# Alberts_NeoPixel_Ring.net
KiCad netlist of a schematic drawn in EAGLE
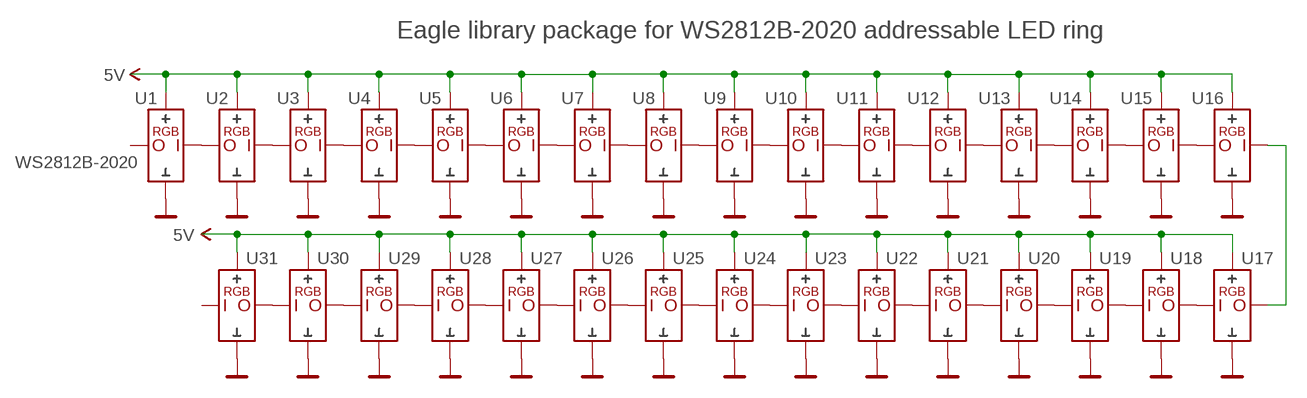
[diagram p0: schematic, sheet 1]

(export (version "E")
  (design (tool "Eeschema 10.0.6"))
  (components
    (comp (ref "U1")
      (value "WS2812B-2020")
      (footprint "eagle-import:LED-WS2812B-2020-RING")
      (libsource (lib "eagle-import") (part "LED-ADDRESSABLE16MM"))
    )
    (comp (ref "U2")
      (value "LED-ADDRESSABLE16MM")
      (footprint "eagle-import:LED-WS2812B-2020-RING")
      (libsource (lib "eagle-import") (part "LED-ADDRESSABLE16MM"))
    )
    (comp (ref "U3")
      (value "LED-ADDRESSABLE16MM")
      (footprint "eagle-import:LED-WS2812B-2020-RING")
      (libsource (lib "eagle-import") (part "LED-ADDRESSABLE16MM"))
    )
    (comp (ref "U4")
      (value "LED-ADDRESSABLE16MM")
      (footprint "eagle-import:LED-WS2812B-2020-RING")
      (libsource (lib "eagle-import") (part "LED-ADDRESSABLE16MM"))
    )
    (comp (ref "U5")
      (value "LED-ADDRESSABLE16MM")
      (footprint "eagle-import:LED-WS2812B-2020-RING")
      (libsource (lib "eagle-import") (part "LED-ADDRESSABLE16MM"))
    )
    (comp (ref "U6")
      (value "LED-ADDRESSABLE16MM")
      (footprint "eagle-import:LED-WS2812B-2020-RING")
      (libsource (lib "eagle-import") (part "LED-ADDRESSABLE16MM"))
    )
    (comp (ref "U7")
      (value "LED-ADDRESSABLE16MM")
      (footprint "eagle-import:LED-WS2812B-2020-RING")
      (libsource (lib "eagle-import") (part "LED-ADDRESSABLE16MM"))
    )
    (comp (ref "U8")
      (value "LED-ADDRESSABLE16MM")
      (footprint "eagle-import:LED-WS2812B-2020-RING")
      (libsource (lib "eagle-import") (part "LED-ADDRESSABLE16MM"))
    )
    (comp (ref "U9")
      (value "LED-ADDRESSABLE16MM")
      (footprint "eagle-import:LED-WS2812B-2020-RING")
      (libsource (lib "eagle-import") (part "LED-ADDRESSABLE16MM"))
    )
    (comp (ref "U10")
      (value "LED-ADDRESSABLE16MM")
      (footprint "eagle-import:LED-WS2812B-2020-RING")
      (libsource (lib "eagle-import") (part "LED-ADDRESSABLE16MM"))
    )
    (comp (ref "U11")
      (value "LED-ADDRESSABLE16MM")
      (footprint "eagle-import:LED-WS2812B-2020-RING")
      (libsource (lib "eagle-import") (part "LED-ADDRESSABLE16MM"))
    )
    (comp (ref "U12")
      (value "LED-ADDRESSABLE16MM")
      (footprint "eagle-import:LED-WS2812B-2020-RING")
      (libsource (lib "eagle-import") (part "LED-ADDRESSABLE16MM"))
    )
    (comp (ref "U13")
      (value "LED-ADDRESSABLE16MM")
      (footprint "eagle-import:LED-WS2812B-2020-RING")
      (libsource (lib "eagle-import") (part "LED-ADDRESSABLE16MM"))
    )
    (comp (ref "U14")
      (value "LED-ADDRESSABLE16MM")
      (footprint "eagle-import:LED-WS2812B-2020-RING")
      (libsource (lib "eagle-import") (part "LED-ADDRESSABLE16MM"))
    )
    (comp (ref "U15")
      (value "LED-ADDRESSABLE16MM")
      (footprint "eagle-import:LED-WS2812B-2020-RING")
      (libsource (lib "eagle-import") (part "LED-ADDRESSABLE16MM"))
    )
    (comp (ref "U16")
      (value "LED-ADDRESSABLE16MM")
      (footprint "eagle-import:LED-WS2812B-2020-RING")
      (libsource (lib "eagle-import") (part "LED-ADDRESSABLE16MM"))
    )
    (comp (ref "U17")
      (value "LED-ADDRESSABLE16MM")
      (footprint "eagle-import:LED-WS2812B-2020-RING")
      (libsource (lib "eagle-import") (part "LED-ADDRESSABLE16MM"))
    )
    (comp (ref "U18")
      (value "LED-ADDRESSABLE16MM")
      (footprint "eagle-import:LED-WS2812B-2020-RING")
      (libsource (lib "eagle-import") (part "LED-ADDRESSABLE16MM"))
    )
    (comp (ref "U19")
      (value "LED-ADDRESSABLE16MM")
      (footprint "eagle-import:LED-WS2812B-2020-RING")
      (libsource (lib "eagle-import") (part "LED-ADDRESSABLE16MM"))
    )
    (comp (ref "U20")
      (value "LED-ADDRESSABLE16MM")
      (footprint "eagle-import:LED-WS2812B-2020-RING")
      (libsource (lib "eagle-import") (part "LED-ADDRESSABLE16MM"))
    )
    (comp (ref "U21")
      (value "LED-ADDRESSABLE16MM")
      (footprint "eagle-import:LED-WS2812B-2020-RING")
      (libsource (lib "eagle-import") (part "LED-ADDRESSABLE16MM"))
    )
    (comp (ref "U22")
      (value "LED-ADDRESSABLE16MM")
      (footprint "eagle-import:LED-WS2812B-2020-RING")
      (libsource (lib "eagle-import") (part "LED-ADDRESSABLE16MM"))
    )
    (comp (ref "U23")
      (value "LED-ADDRESSABLE16MM")
      (footprint "eagle-import:LED-WS2812B-2020-RING")
      (libsource (lib "eagle-import") (part "LED-ADDRESSABLE16MM"))
    )
    (comp (ref "U24")
      (value "LED-ADDRESSABLE16MM")
      (footprint "eagle-import:LED-WS2812B-2020-RING")
      (libsource (lib "eagle-import") (part "LED-ADDRESSABLE16MM"))
    )
    (comp (ref "U25")
      (value "LED-ADDRESSABLE16MM")
      (footprint "eagle-import:LED-WS2812B-2020-RING")
      (libsource (lib "eagle-import") (part "LED-ADDRESSABLE16MM"))
    )
    (comp (ref "U26")
      (value "LED-ADDRESSABLE16MM")
      (footprint "eagle-import:LED-WS2812B-2020-RING")
      (libsource (lib "eagle-import") (part "LED-ADDRESSABLE16MM"))
    )
    (comp (ref "U27")
      (value "LED-ADDRESSABLE16MM")
      (footprint "eagle-import:LED-WS2812B-2020-RING")
      (libsource (lib "eagle-import") (part "LED-ADDRESSABLE16MM"))
    )
    (comp (ref "U28")
      (value "LED-ADDRESSABLE16MM")
      (footprint "eagle-import:LED-WS2812B-2020-RING")
      (libsource (lib "eagle-import") (part "LED-ADDRESSABLE16MM"))
    )
    (comp (ref "U29")
      (value "LED-ADDRESSABLE16MM")
      (footprint "eagle-import:LED-WS2812B-2020-RING")
      (libsource (lib "eagle-import") (part "LED-ADDRESSABLE16MM"))
    )
    (comp (ref "U30")
      (value "LED-ADDRESSABLE16MM")
      (footprint "eagle-import:LED-WS2812B-2020-RING")
      (libsource (lib "eagle-import") (part "LED-ADDRESSABLE16MM"))
    )
    (comp (ref "U31")
      (value "LED-ADDRESSABLE16MM")
      (footprint "eagle-import:LED-WS2812B-2020-RING")
      (libsource (lib "eagle-import") (part "LED-ADDRESSABLE16MM"))
    )
  )
  (nets
    (net (code "1") (name "/5V") (class "Default")
      (node (ref "U1") (pin "+") (pinfunction "VDD_+") (pintype "bidirectional"))
      (node (ref "U10") (pin "+") (pinfunction "VDD_+") (pintype "bidirectional"))
      (node (ref "U11") (pin "+") (pinfunction "VDD_+") (pintype "bidirectional"))
      (node (ref "U12") (pin "+") (pinfunction "VDD_+") (pintype "bidirectional"))
      (node (ref "U13") (pin "+") (pinfunction "VDD_+") (pintype "bidirectional"))
      (node (ref "U14") (pin "+") (pinfunction "VDD_+") (pintype "bidirectional"))
      (node (ref "U15") (pin "+") (pinfunction "VDD_+") (pintype "bidirectional"))
      (node (ref "U16") (pin "+") (pinfunction "VDD_+") (pintype "bidirectional"))
      (node (ref "U17") (pin "+") (pinfunction "VDD_+") (pintype "bidirectional"))
      (node (ref "U18") (pin "+") (pinfunction "VDD_+") (pintype "bidirectional"))
      (node (ref "U19") (pin "+") (pinfunction "VDD_+") (pintype "bidirectional"))
      (node (ref "U2") (pin "+") (pinfunction "VDD_+") (pintype "bidirectional"))
      (node (ref "U20") (pin "+") (pinfunction "VDD_+") (pintype "bidirectional"))
      (node (ref "U21") (pin "+") (pinfunction "VDD_+") (pintype "bidirectional"))
      (node (ref "U22") (pin "+") (pinfunction "VDD_+") (pintype "bidirectional"))
      (node (ref "U23") (pin "+") (pinfunction "VDD_+") (pintype "bidirectional"))
      (node (ref "U24") (pin "+") (pinfunction "VDD_+") (pintype "bidirectional"))
      (node (ref "U25") (pin "+") (pinfunction "VDD_+") (pintype "bidirectional"))
      (node (ref "U26") (pin "+") (pinfunction "VDD_+") (pintype "bidirectional"))
      (node (ref "U27") (pin "+") (pinfunction "VDD_+") (pintype "bidirectional"))
      (node (ref "U28") (pin "+") (pinfunction "VDD_+") (pintype "bidirectional"))
      (node (ref "U29") (pin "+") (pinfunction "VDD_+") (pintype "bidirectional"))
      (node (ref "U3") (pin "+") (pinfunction "VDD_+") (pintype "bidirectional"))
      (node (ref "U30") (pin "+") (pinfunction "VDD_+") (pintype "bidirectional"))
      (node (ref "U31") (pin "+") (pinfunction "VDD_+") (pintype "bidirectional"))
      (node (ref "U4") (pin "+") (pinfunction "VDD_+") (pintype "bidirectional"))
      (node (ref "U5") (pin "+") (pinfunction "VDD_+") (pintype "bidirectional"))
      (node (ref "U6") (pin "+") (pinfunction "VDD_+") (pintype "bidirectional"))
      (node (ref "U7") (pin "+") (pinfunction "VDD_+") (pintype "bidirectional"))
      (node (ref "U8") (pin "+") (pinfunction "VDD_+") (pintype "bidirectional"))
      (node (ref "U9") (pin "+") (pinfunction "VDD_+") (pintype "bidirectional"))
    )
    (net (code "2") (name "GND") (class "Default")
      (node (ref "U1") (pin "GND") (pinfunction "GND_GND") (pintype "bidirectional"))
      (node (ref "U10") (pin "GND") (pinfunction "GND_GND") (pintype "bidirectional"))
      (node (ref "U11") (pin "GND") (pinfunction "GND_GND") (pintype "bidirectional"))
      (node (ref "U12") (pin "GND") (pinfunction "GND_GND") (pintype "bidirectional"))
      (node (ref "U13") (pin "GND") (pinfunction "GND_GND") (pintype "bidirectional"))
      (node (ref "U14") (pin "GND") (pinfunction "GND_GND") (pintype "bidirectional"))
      (node (ref "U15") (pin "GND") (pinfunction "GND_GND") (pintype "bidirectional"))
      (node (ref "U16") (pin "GND") (pinfunction "GND_GND") (pintype "bidirectional"))
      (node (ref "U17") (pin "GND") (pinfunction "GND_GND") (pintype "bidirectional"))
      (node (ref "U18") (pin "GND") (pinfunction "GND_GND") (pintype "bidirectional"))
      (node (ref "U19") (pin "GND") (pinfunction "GND_GND") (pintype "bidirectional"))
      (node (ref "U2") (pin "GND") (pinfunction "GND_GND") (pintype "bidirectional"))
      (node (ref "U20") (pin "GND") (pinfunction "GND_GND") (pintype "bidirectional"))
      (node (ref "U21") (pin "GND") (pinfunction "GND_GND") (pintype "bidirectional"))
      (node (ref "U22") (pin "GND") (pinfunction "GND_GND") (pintype "bidirectional"))
      (node (ref "U23") (pin "GND") (pinfunction "GND_GND") (pintype "bidirectional"))
      (node (ref "U24") (pin "GND") (pinfunction "GND_GND") (pintype "bidirectional"))
      (node (ref "U25") (pin "GND") (pinfunction "GND_GND") (pintype "bidirectional"))
      (node (ref "U26") (pin "GND") (pinfunction "GND_GND") (pintype "bidirectional"))
      (node (ref "U27") (pin "GND") (pinfunction "GND_GND") (pintype "bidirectional"))
      (node (ref "U28") (pin "GND") (pinfunction "GND_GND") (pintype "bidirectional"))
      (node (ref "U29") (pin "GND") (pinfunction "GND_GND") (pintype "bidirectional"))
      (node (ref "U3") (pin "GND") (pinfunction "GND_GND") (pintype "bidirectional"))
      (node (ref "U30") (pin "GND") (pinfunction "GND_GND") (pintype "bidirectional"))
      (node (ref "U31") (pin "GND") (pinfunction "GND_GND") (pintype "bidirectional"))
      (node (ref "U4") (pin "GND") (pinfunction "GND_GND") (pintype "bidirectional"))
      (node (ref "U5") (pin "GND") (pinfunction "GND_GND") (pintype "bidirectional"))
      (node (ref "U6") (pin "GND") (pinfunction "GND_GND") (pintype "bidirectional"))
      (node (ref "U7") (pin "GND") (pinfunction "GND_GND") (pintype "bidirectional"))
      (node (ref "U8") (pin "GND") (pinfunction "GND_GND") (pintype "bidirectional"))
      (node (ref "U9") (pin "GND") (pinfunction "GND_GND") (pintype "bidirectional"))
    )
    (net (code "3") (name "Net-(U1-PadDI)") (class "Default")
      (node (ref "U1") (pin "DI") (pinfunction "DI_DI") (pintype "bidirectional"))
      (node (ref "U2") (pin "DO") (pinfunction "DO_DO") (pintype "bidirectional"))
    )
    (net (code "4") (name "Net-(U2-PadDI)") (class "Default")
      (node (ref "U2") (pin "DI") (pinfunction "DI_DI") (pintype "bidirectional"))
      (node (ref "U3") (pin "DO") (pinfunction "DO_DO") (pintype "bidirectional"))
    )
    (net (code "5") (name "Net-(U3-PadDI)") (class "Default")
      (node (ref "U3") (pin "DI") (pinfunction "DI_DI") (pintype "bidirectional"))
      (node (ref "U4") (pin "DO") (pinfunction "DO_DO") (pintype "bidirectional"))
    )
    (net (code "6") (name "Net-(U4-PadDI)") (class "Default")
      (node (ref "U4") (pin "DI") (pinfunction "DI_DI") (pintype "bidirectional"))
      (node (ref "U5") (pin "DO") (pinfunction "DO_DO") (pintype "bidirectional"))
    )
    (net (code "7") (name "Net-(U5-PadDI)") (class "Default")
      (node (ref "U5") (pin "DI") (pinfunction "DI_DI") (pintype "bidirectional"))
      (node (ref "U6") (pin "DO") (pinfunction "DO_DO") (pintype "bidirectional"))
    )
    (net (code "8") (name "Net-(U6-PadDI)") (class "Default")
      (node (ref "U6") (pin "DI") (pinfunction "DI_DI") (pintype "bidirectional"))
      (node (ref "U7") (pin "DO") (pinfunction "DO_DO") (pintype "bidirectional"))
    )
    (net (code "9") (name "Net-(U7-PadDI)") (class "Default")
      (node (ref "U7") (pin "DI") (pinfunction "DI_DI") (pintype "bidirectional"))
      (node (ref "U8") (pin "DO") (pinfunction "DO_DO") (pintype "bidirectional"))
    )
    (net (code "10") (name "Net-(U8-PadDI)") (class "Default")
      (node (ref "U8") (pin "DI") (pinfunction "DI_DI") (pintype "bidirectional"))
      (node (ref "U9") (pin "DO") (pinfunction "DO_DO") (pintype "bidirectional"))
    )
    (net (code "11") (name "Net-(U10-PadDI)") (class "Default")
      (node (ref "U10") (pin "DI") (pinfunction "DI_DI") (pintype "bidirectional"))
      (node (ref "U11") (pin "DO") (pinfunction "DO_DO") (pintype "bidirectional"))
    )
    (net (code "12") (name "Net-(U10-PadDO)") (class "Default")
      (node (ref "U10") (pin "DO") (pinfunction "DO_DO") (pintype "bidirectional"))
      (node (ref "U9") (pin "DI") (pinfunction "DI_DI") (pintype "bidirectional"))
    )
    (net (code "13") (name "Net-(U11-PadDI)") (class "Default")
      (node (ref "U11") (pin "DI") (pinfunction "DI_DI") (pintype "bidirectional"))
      (node (ref "U12") (pin "DO") (pinfunction "DO_DO") (pintype "bidirectional"))
    )
    (net (code "14") (name "Net-(U12-PadDI)") (class "Default")
      (node (ref "U12") (pin "DI") (pinfunction "DI_DI") (pintype "bidirectional"))
      (node (ref "U13") (pin "DO") (pinfunction "DO_DO") (pintype "bidirectional"))
    )
    (net (code "15") (name "Net-(U13-PadDI)") (class "Default")
      (node (ref "U13") (pin "DI") (pinfunction "DI_DI") (pintype "bidirectional"))
      (node (ref "U14") (pin "DO") (pinfunction "DO_DO") (pintype "bidirectional"))
    )
    (net (code "16") (name "Net-(U14-PadDI)") (class "Default")
      (node (ref "U14") (pin "DI") (pinfunction "DI_DI") (pintype "bidirectional"))
      (node (ref "U15") (pin "DO") (pinfunction "DO_DO") (pintype "bidirectional"))
    )
    (net (code "17") (name "Net-(U15-PadDI)") (class "Default")
      (node (ref "U15") (pin "DI") (pinfunction "DI_DI") (pintype "bidirectional"))
      (node (ref "U16") (pin "DO") (pinfunction "DO_DO") (pintype "bidirectional"))
    )
    (net (code "18") (name "Net-(U16-PadDI)") (class "Default")
      (node (ref "U16") (pin "DI") (pinfunction "DI_DI") (pintype "bidirectional"))
      (node (ref "U17") (pin "DO") (pinfunction "DO_DO") (pintype "bidirectional"))
    )
    (net (code "19") (name "Net-(U17-PadDI)") (class "Default")
      (node (ref "U17") (pin "DI") (pinfunction "DI_DI") (pintype "bidirectional"))
      (node (ref "U18") (pin "DO") (pinfunction "DO_DO") (pintype "bidirectional"))
    )
    (net (code "20") (name "Net-(U18-PadDI)") (class "Default")
      (node (ref "U18") (pin "DI") (pinfunction "DI_DI") (pintype "bidirectional"))
      (node (ref "U19") (pin "DO") (pinfunction "DO_DO") (pintype "bidirectional"))
    )
    (net (code "21") (name "Net-(U19-PadDI)") (class "Default")
      (node (ref "U19") (pin "DI") (pinfunction "DI_DI") (pintype "bidirectional"))
      (node (ref "U20") (pin "DO") (pinfunction "DO_DO") (pintype "bidirectional"))
    )
    (net (code "22") (name "Net-(U20-PadDI)") (class "Default")
      (node (ref "U20") (pin "DI") (pinfunction "DI_DI") (pintype "bidirectional"))
      (node (ref "U21") (pin "DO") (pinfunction "DO_DO") (pintype "bidirectional"))
    )
    (net (code "23") (name "Net-(U21-PadDI)") (class "Default")
      (node (ref "U21") (pin "DI") (pinfunction "DI_DI") (pintype "bidirectional"))
      (node (ref "U22") (pin "DO") (pinfunction "DO_DO") (pintype "bidirectional"))
    )
    (net (code "24") (name "Net-(U22-PadDI)") (class "Default")
      (node (ref "U22") (pin "DI") (pinfunction "DI_DI") (pintype "bidirectional"))
      (node (ref "U23") (pin "DO") (pinfunction "DO_DO") (pintype "bidirectional"))
    )
    (net (code "25") (name "Net-(U23-PadDI)") (class "Default")
      (node (ref "U23") (pin "DI") (pinfunction "DI_DI") (pintype "bidirectional"))
      (node (ref "U24") (pin "DO") (pinfunction "DO_DO") (pintype "bidirectional"))
    )
    (net (code "26") (name "Net-(U24-PadDI)") (class "Default")
      (node (ref "U24") (pin "DI") (pinfunction "DI_DI") (pintype "bidirectional"))
      (node (ref "U25") (pin "DO") (pinfunction "DO_DO") (pintype "bidirectional"))
    )
    (net (code "27") (name "Net-(U25-PadDI)") (class "Default")
      (node (ref "U25") (pin "DI") (pinfunction "DI_DI") (pintype "bidirectional"))
      (node (ref "U26") (pin "DO") (pinfunction "DO_DO") (pintype "bidirectional"))
    )
    (net (code "28") (name "Net-(U26-PadDI)") (class "Default")
      (node (ref "U26") (pin "DI") (pinfunction "DI_DI") (pintype "bidirectional"))
      (node (ref "U27") (pin "DO") (pinfunction "DO_DO") (pintype "bidirectional"))
    )
    (net (code "29") (name "Net-(U27-PadDI)") (class "Default")
      (node (ref "U27") (pin "DI") (pinfunction "DI_DI") (pintype "bidirectional"))
      (node (ref "U28") (pin "DO") (pinfunction "DO_DO") (pintype "bidirectional"))
    )
    (net (code "30") (name "Net-(U28-PadDI)") (class "Default")
      (node (ref "U28") (pin "DI") (pinfunction "DI_DI") (pintype "bidirectional"))
      (node (ref "U29") (pin "DO") (pinfunction "DO_DO") (pintype "bidirectional"))
    )
    (net (code "31") (name "Net-(U29-PadDI)") (class "Default")
      (node (ref "U29") (pin "DI") (pinfunction "DI_DI") (pintype "bidirectional"))
      (node (ref "U30") (pin "DO") (pinfunction "DO_DO") (pintype "bidirectional"))
    )
    (net (code "32") (name "Net-(U30-PadDI)") (class "Default")
      (node (ref "U30") (pin "DI") (pinfunction "DI_DI") (pintype "bidirectional"))
      (node (ref "U31") (pin "DO") (pinfunction "DO_DO") (pintype "bidirectional"))
    )
    (net (code "33") (name "unconnected-(U1-PadDO)") (class "Default")
      (node (ref "U1") (pin "DO") (pinfunction "DO_DO") (pintype "bidirectional"))
    )
    (net (code "34") (name "unconnected-(U31-PadDI)") (class "Default")
      (node (ref "U31") (pin "DI") (pinfunction "DI_DI") (pintype "bidirectional"))
    )
  )
)
